# design.net
KiCad netlist of a schematic drawn in EasyEDA Pro
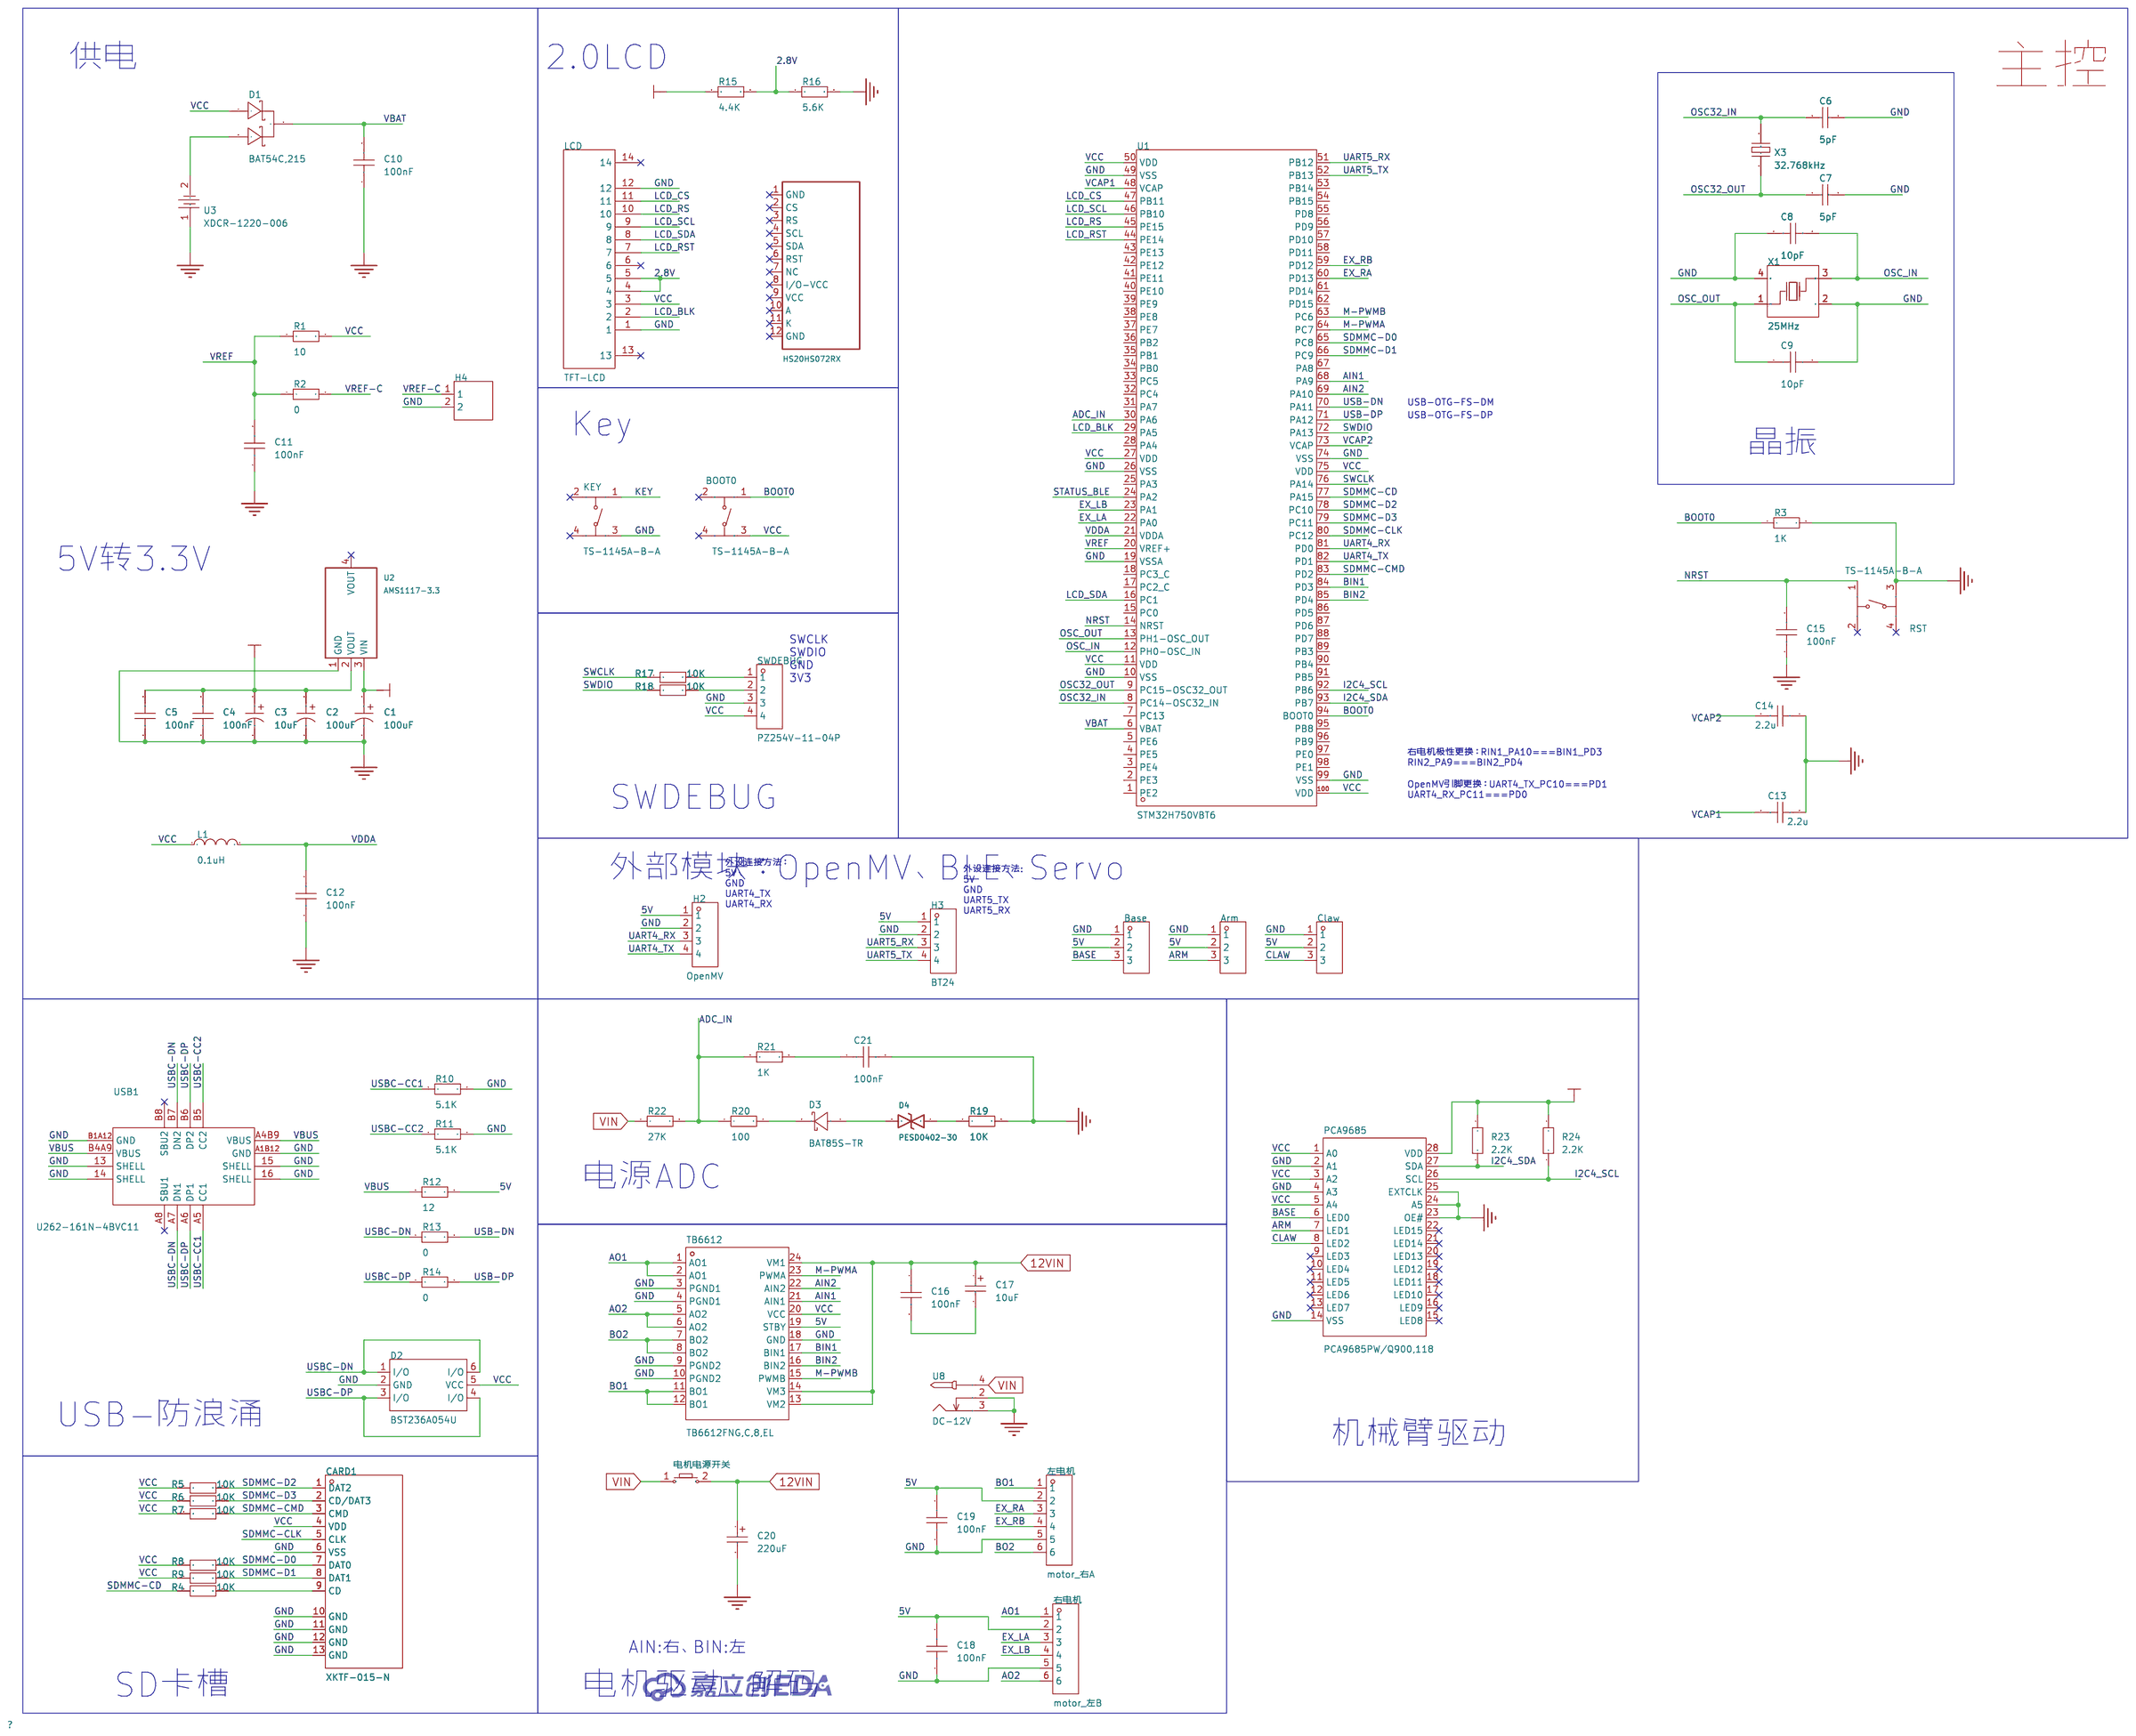
[diagram p0: schematic sheet]

(export (version "E")
  (design (tool "Eeschema 10.0.6"))
  (components
    (comp (ref "Arm")
      (value "~")
      (footprint "easyedapro:HDR-TH_3P-P2.54-V-M")
      (libsource (lib "easyedapro") (part "HDR-M_2.54_1x3P"))
    )
    (comp (ref "Base")
      (value "~")
      (footprint "easyedapro:HDR-TH_3P-P2.54-V-M")
      (libsource (lib "easyedapro") (part "HDR-M_2.54_1x3P"))
    )
    (comp (ref "BOOT0")
      (value "TS-1145A-B-A")
      (footprint "easyedapro:SW-SMD_4P-L4.2-W3.2-P2.15-LS5.2")
      (fields (field (name "Manufacturer") "XKB Connectivity(中国星坤)"))
      (libsource (lib "easyedapro") (part "TS-1145A-B-A"))
    )
    (comp (ref "C1")
      (value "100uF")
      (footprint "easyedapro:CAP-SMD_L3.5-W2.8-FD")
      (description "容值:10uF;精度:±10%;额定电压:10V;等效串联电阻:-;")
      (fields
        (field (name "Manufacturer Part") "CA45-B-10V-10UF-K")
        (field (name "Manufacturer") "CEC(振华新云)")
      )
      (libsource (lib "easyedapro") (part "CA45-B-10V-10UF-K"))
    )
    (comp (ref "C2")
      (value "100uF")
      (footprint "easyedapro:CAP-SMD_L3.5-W2.8-FD")
      (description "容值:10uF;精度:±10%;额定电压:10V;等效串联电阻:-;")
      (fields
        (field (name "Manufacturer Part") "CA45-B-10V-10UF-K")
        (field (name "Manufacturer") "CEC(振华新云)")
      )
      (libsource (lib "easyedapro") (part "CA45-B-10V-10UF-K"))
    )
    (comp (ref "C3")
      (value "10uF")
      (footprint "easyedapro:CAP-SMD_L3.5-W2.8-FD")
      (description "容值:10uF;精度:±10%;额定电压:10V;等效串联电阻:-;")
      (fields
        (field (name "Manufacturer Part") "CA45-B-10V-10UF-K")
        (field (name "Manufacturer") "CEC(振华新云)")
      )
      (libsource (lib "easyedapro") (part "CA45-B-10V-10UF-K"))
    )
    (comp (ref "C4")
      (value "100nF")
      (footprint "easyedapro:C0402")
      (libsource (lib "easyedapro") (part "Capacitance"))
    )
    (comp (ref "C5")
      (value "100nF")
      (footprint "easyedapro:C0402")
      (libsource (lib "easyedapro") (part "Capacitance"))
    )
    (comp (ref "C6")
      (value "5pF")
      (footprint "easyedapro:C0402")
      (description "容值:5pF;额定电压:50V;温度系数:C0G;")
      (fields (field (name "Manufacturer Part") "0402CG5R0C500NT") (field (name "Manufacturer") "FH(风华)"))
      (libsource (lib "easyedapro") (part "0402CG5R0C500NT"))
    )
    (comp (ref "C7")
      (value "5pF")
      (footprint "easyedapro:C0402")
      (description "容值:5pF;额定电压:50V;温度系数:C0G;")
      (fields (field (name "Manufacturer Part") "0402CG5R0C500NT") (field (name "Manufacturer") "FH(风华)"))
      (libsource (lib "easyedapro") (part "0402CG5R0C500NT"))
    )
    (comp (ref "C8")
      (value "10pF")
      (footprint "easyedapro:C0402")
      (description "容值:10pF;精度:±5%;额定电压:50V;温度系数:C0G;")
      (fields
        (field (name "Manufacturer Part") "CL05C100JB5NNNC")
        (field (name "Manufacturer") "SAMSUNG(三星)")
      )
      (libsource (lib "easyedapro") (part "CL05C100JB5NNNC"))
    )
    (comp (ref "C9")
      (value "10pF")
      (footprint "easyedapro:C0402")
      (description "容值:10pF;精度:±5%;额定电压:50V;温度系数:C0G;")
      (fields
        (field (name "Manufacturer Part") "CL05C100JB5NNNC")
        (field (name "Manufacturer") "SAMSUNG(三星)")
      )
      (libsource (lib "easyedapro") (part "CL05C100JB5NNNC"))
    )
    (comp (ref "C10")
      (value "100nF")
      (footprint "easyedapro:C0402")
      (libsource (lib "easyedapro") (part "Capacitance"))
    )
    (comp (ref "C11")
      (value "100nF")
      (footprint "easyedapro:C0402")
      (libsource (lib "easyedapro") (part "Capacitance"))
    )
    (comp (ref "C12")
      (value "100nF")
      (footprint "easyedapro:C0402")
      (libsource (lib "easyedapro") (part "Capacitance"))
    )
    (comp (ref "C13")
      (value "2.2u")
      (footprint "easyedapro:C0402")
      (libsource (lib "easyedapro") (part "Capacitance"))
    )
    (comp (ref "C14")
      (value "2.2u")
      (footprint "easyedapro:C0402")
      (libsource (lib "easyedapro") (part "Capacitance"))
    )
    (comp (ref "C15")
      (value "100nF")
      (footprint "easyedapro:C0402")
      (libsource (lib "easyedapro") (part "Capacitance"))
    )
    (comp (ref "C16")
      (value "100nF")
      (footprint "easyedapro:C0402")
      (libsource (lib "easyedapro") (part "Capacitance"))
    )
    (comp (ref "C17")
      (value "10uF")
      (footprint "easyedapro:C_Ele_SMD_3x5.4mm")
      (libsource (lib "easyedapro") (part "CAP"))
    )
    (comp (ref "C18")
      (value "100nF")
      (footprint "easyedapro:C0402")
      (libsource (lib "easyedapro") (part "Capacitance"))
    )
    (comp (ref "C19")
      (value "100nF")
      (footprint "easyedapro:C0402")
      (libsource (lib "easyedapro") (part "Capacitance"))
    )
    (comp (ref "C20")
      (value "220uF")
      (footprint "easyedapro:C_Ele_SMD_3x5.4mm")
      (libsource (lib "easyedapro") (part "CAP"))
    )
    (comp (ref "C21")
      (value "100nF")
      (footprint "easyedapro:C0402")
      (libsource (lib "easyedapro") (part "Capacitance"))
    )
    (comp (ref "CARD1")
      (value "XKTF-015-N")
      (footprint "easyedapro:TF-SMD_XKTF-015-N")
      (description "卡连接方式:自弹式;卡类型:MicroSD卡(TF卡);连接器类型:卡座;本体最大高度:2mm;工作温度:-25°C~+90°C;")
      (fields (field (name "Manufacturer") "XKB Connection(中国星坤)"))
      (libsource (lib "easyedapro") (part "XKTF-015-N"))
    )
    (comp (ref "Claw")
      (value "~")
      (footprint "easyedapro:HDR-TH_3P-P2.54-V-M")
      (libsource (lib "easyedapro") (part "HDR-M_2.54_1x3P"))
    )
    (comp (ref "D1")
      (value "BAT54C,215")
      (footprint "easyedapro:SOT-23-3_L2.9-W1.6-P1.90-LS2.8-BR")
      (description "二极管配置:1对共阴极;正向压降(Vf):800mV@100mA;直流反向耐压(Vr):30V;整流电流:200mA;")
      (fields (field (name "Manufacturer") "Nexperia(安世)"))
      (libsource (lib "easyedapro") (part "BAT54C,215"))
    )
    (comp (ref "D2")
      (value "BST236A054U")
      (footprint "easyedapro:SOT-23-6_L2.9-W1.6-P0.95-LS2.8-BR")
      (description "极性:-;反向截止电压(Vrwm):5V;钳位电压:13V;峰值脉冲电流(Ipp):3.5A;峰值脉冲功率(Ppp):45W@8/20us;击穿电压:6V;")
      (fields (field (name "Manufacturer") "BORN(伯恩半导体)"))
      (libsource (lib "easyedapro") (part "BST236A054U"))
    )
    (comp (ref "D3")
      (value "BAT85S-TR")
      (footprint "easyedapro:DO-35_BD1.7-L3.8-P7.8-D0.5-FD")
      (description "二极管配置:1个独立式;正向压降(Vf):800mV@100mA;直流反向耐压(Vr):30V;整流电流:200mA;")
      (fields (field (name "Manufacturer") "VISHAY(威世)"))
      (libsource (lib "easyedapro") (part "BAT85S-TR"))
    )
    (comp (ref "D4")
      (value "PESD0402-30")
      (footprint "easyedapro:D0402-BI")
      (description "极性:双向;反向截止电压(Vrwm):30V;钳位电压:40V;")
      (fields (field (name "Manufacturer") "R+O(宏嘉诚)"))
      (libsource (lib "easyedapro") (part "PESD0402-30"))
    )
    (comp (ref "H2")
      (value "OpenMV")
      (footprint "easyedapro:HDR-TH_4P-P2.54-V-M")
      (fields (field (name "Manufacturer") "XFCN(兴飞)"))
      (libsource (lib "easyedapro") (part "PZ254V-11-04P_C2691448"))
    )
    (comp (ref "H3")
      (value "BT24")
      (footprint "easyedapro:HDR-TH_4P-P2.54-V-M")
      (fields (field (name "Manufacturer") "XFCN(兴飞)"))
      (libsource (lib "easyedapro") (part "PZ254V-11-04P_C2691448"))
    )
    (comp (ref "H4")
      (value "~")
      (footprint "easyedapro:HDR-TH_2P-P2.54-V-M-1")
      (libsource (lib "easyedapro") (part "210S-1*2P L=11.6MMGold-plated black"))
    )
    (comp (ref "KEY")
      (value "TS-1145A-B-A")
      (footprint "easyedapro:SW-SMD_4P-L4.2-W3.2-P2.15-LS5.2")
      (fields (field (name "Manufacturer") "XKB Connectivity(中国星坤)"))
      (libsource (lib "easyedapro") (part "TS-1145A-B-A"))
    )
    (comp (ref "L1")
      (value "0.1uH")
      (footprint "easyedapro:L0805")
      (libsource (lib "easyedapro") (part "SDFL2012S100KTF"))
    )
    (comp (ref "LCD")
      (value "TFT-LCD")
      (footprint "easyedapro:FPC-SMD_AFC01-S12FCA-00")
      (description "锁定特性:翻盖式;触点类型:下接;触点数量:12P;间距:0.5mm;安装方式:卧贴;")
      (fields (field (name "Manufacturer") "JS(钜硕电子)"))
      (libsource (lib "easyedapro") (part "AFC01-S12FCA-00"))
    )
    (comp (ref "PCA9685")
      (value "PCA9685PW/Q900,118")
      (footprint "easyedapro:TSSOP-28_L9.7-W4.4-P0.65-LS6.4-BL")
      (description "类型:-;工作电压(DC):2.3V~5.5V;通道数:16;输出电压:5.5V;输出电流:25mA;调光:PWM;")
      (fields (field (name "Manufacturer") "NXP(恩智浦)"))
      (libsource (lib "easyedapro") (part "PCA9685PW/Q900,118"))
    )
    (comp (ref "R1") (value "10") (footprint "easyedapro:R0402") (libsource (lib "easyedapro") (part "电阻")))
    (comp (ref "R2") (value "0") (footprint "easyedapro:R0402") (libsource (lib "easyedapro") (part "电阻")))
    (comp (ref "R3") (value "1K") (footprint "easyedapro:R0402") (libsource (lib "easyedapro") (part "电阻")))
    (comp (ref "R4") (value "10K") (footprint "easyedapro:R0402") (libsource (lib "easyedapro") (part "电阻")))
    (comp (ref "R5") (value "10K") (footprint "easyedapro:R0402") (libsource (lib "easyedapro") (part "电阻")))
    (comp (ref "R6") (value "10K") (footprint "easyedapro:R0402") (libsource (lib "easyedapro") (part "电阻")))
    (comp (ref "R7") (value "10K") (footprint "easyedapro:R0402") (libsource (lib "easyedapro") (part "电阻")))
    (comp (ref "R8") (value "10K") (footprint "easyedapro:R0402") (libsource (lib "easyedapro") (part "电阻")))
    (comp (ref "R9") (value "10K") (footprint "easyedapro:R0402") (libsource (lib "easyedapro") (part "电阻")))
    (comp (ref "R10")
      (value "5.1K")
      (footprint "easyedapro:R0402")
      (libsource (lib "easyedapro") (part "电阻"))
    )
    (comp (ref "R11")
      (value "5.1K")
      (footprint "easyedapro:R0402")
      (libsource (lib "easyedapro") (part "电阻"))
    )
    (comp (ref "R12") (value "12") (footprint "easyedapro:R0402") (libsource (lib "easyedapro") (part "电阻")))
    (comp (ref "R13") (value "0") (footprint "easyedapro:R0402") (libsource (lib "easyedapro") (part "电阻")))
    (comp (ref "R14") (value "0") (footprint "easyedapro:R0402") (libsource (lib "easyedapro") (part "电阻")))
    (comp (ref "R15")
      (value "4.4K")
      (footprint "easyedapro:R0402")
      (libsource (lib "easyedapro") (part "电阻"))
    )
    (comp (ref "R16")
      (value "5.6K")
      (footprint "easyedapro:R0402")
      (libsource (lib "easyedapro") (part "电阻"))
    )
    (comp (ref "R17") (value "10K") (footprint "easyedapro:R0402") (libsource (lib "easyedapro") (part "电阻")))
    (comp (ref "R18") (value "10K") (footprint "easyedapro:R0402") (libsource (lib "easyedapro") (part "电阻")))
    (comp (ref "R19") (value "10K") (footprint "easyedapro:R0402") (libsource (lib "easyedapro") (part "电阻")))
    (comp (ref "R20") (value "100") (footprint "easyedapro:R0402") (libsource (lib "easyedapro") (part "电阻")))
    (comp (ref "R21") (value "1K") (footprint "easyedapro:R0402") (libsource (lib "easyedapro") (part "电阻")))
    (comp (ref "R22") (value "27K") (footprint "easyedapro:R0402") (libsource (lib "easyedapro") (part "电阻")))
    (comp (ref "R23")
      (value "2.2K")
      (footprint "easyedapro:R0402")
      (libsource (lib "easyedapro") (part "电阻"))
    )
    (comp (ref "R24")
      (value "2.2K")
      (footprint "easyedapro:R0402")
      (libsource (lib "easyedapro") (part "电阻"))
    )
    (comp (ref "RST")
      (value "TS-1145A-B-A")
      (footprint "easyedapro:SW-SMD_4P-L4.2-W3.2-P2.15-LS5.2")
      (fields (field (name "Manufacturer") "XKB Connectivity(中国星坤)"))
      (libsource (lib "easyedapro") (part "TS-1145A-B-A"))
    )
    (comp (ref "SWDEBUG")
      (value "PZ254V-11-04P")
      (footprint "easyedapro:HDR-TH_4P-P2.54-V-M")
      (fields (field (name "Manufacturer") "XFCN(兴飞)"))
      (libsource (lib "easyedapro") (part "PZ254V-11-04P_C2691448"))
    )
    (comp (ref "TB6612")
      (value "TB6612FNG,C,8,EL")
      (footprint "easyedapro:SSOP-24_L8.3-W5.6-P0.65-LS7.6-BL")
      (description "TB6612FNG 是一款直流电机驱动 IC，其输出晶体管采用低导通电阻的 LD MOS 结构。两个输入信号 IN1 和 IN2 可选择四种模式之一，如正转、反转、短路制动和停止模式。")
      (fields (field (name "Manufacturer") "TOSHIBA(东芝)"))
      (libsource (lib "easyedapro") (part "TB6612FNG,C,8,EL"))
    )
    (comp (ref "U1")
      (value "STM32H750VBT6")
      (footprint "easyedapro:LQFP-100_L14.0-W14.0-P0.50-LS16.0-BL")
      (description "CPU内核:ARM-M系列;CPU最大主频:480MHz;应用领域:-;")
      (fields (field (name "Manufacturer") "ST(意法半导体)"))
      (libsource (lib "easyedapro") (part "STM32H750VBT6"))
    )
    (comp (ref "U2")
      (value "AMS1117-3.3")
      (footprint "easyedapro:SOT-223-3_L6.5-W3.4-P2.30-LS7.0-BR")
      (description "输出极性:正极;工作电压:15V;输出电压:3.3V;输出电流:1A;电源纹波抑制比(PSRR):72dB@(120Hz);输出类型:固定;")
      (fields (field (name "Manufacturer") "Advanced Monolithic Systems"))
      (libsource (lib "easyedapro") (part "AMS1117-3.3"))
    )
    (comp (ref "U3")
      (value "XDCR-1220-006")
      (footprint "easyedapro:BAT-SMD_CR1220-2ZX")
      (description "连接器类型:电池底座;适用电池规格:CR1220;触头材质:-;触头镀层:金;工作温度:-40°C~+85°C;")
      (fields (field (name "Manufacturer") "LX(连欣科技)"))
      (libsource (lib "easyedapro") (part "XDCR-1220-006"))
    )
    (comp (ref "U7")
      (value "HS20HS072RX")
      (footprint "easyedapro:OLED-SMD_HS20HS072RX")
      (description "核心芯片:ST7789;接口类型:SPI;尺寸(inch):2;像素分辨率:320x240;")
      (fields (field (name "Manufacturer") "HS(汉昇)"))
      (libsource (lib "easyedapro") (part "HS20HS072RX"))
    )
    (comp (ref "U8")
      (value "DC-12V")
      (footprint "easyedapro:DC-IN-TH_DC005-2.5MM")
      (description "连接器类型:DC电源插座;安装方式:弯插;触点内径:2.5mm;触点外径:6.3mm;额定电流:500mA;额定电压:12V;工作温度:-30°C~+70°C;")
      (fields (field (name "Manufacturer") "SHOU HAN(首韩)"))
      (libsource (lib "easyedapro") (part "DC005-2.5"))
    )
    (comp (ref "USB1")
      (value "U262-161N-4BVC11")
      (footprint "easyedapro:USB-3.1-SMD_U262-161N-4BVC11")
      (description "连接器类型:Type-C;协议标准:-;公母:母;安装方式:卧贴;触点数量:16P;端口数量:1;额定电流 - 电源:3A;工作温度:-40°C~+85°C;")
      (fields (field (name "Manufacturer") "XKB Connection(中国星坤)"))
      (libsource (lib "easyedapro") (part "U262-16XN-4BVC11"))
    )
    (comp (ref "X1")
      (value "25MHz")
      (footprint "easyedapro:CRYSTAL-SMD_4P-L3.2-W2.5-BL")
      (description "晶振类型:贴片晶振;频率:25MHz;常温频差:±10ppm;负载电容:12pF;频率稳定度:±20ppm;")
      (fields (field (name "Manufacturer Part") "X322525MOB4SI") (field (name "Manufacturer") "YXC(扬兴晶振)"))
      (libsource (lib "easyedapro") (part "X322525MOB4SI"))
    )
    (comp (ref "X3")
      (value "32.768kHz")
      (footprint "easyedapro:CRYSTAL-SMD_L3.2-W1.5-1")
      (description "频率:32.768kHz;常温频差:±20ppm;负载电容:12.5pF;")
      (fields
        (field (name "Manufacturer Part") "FC-135R 32.7680KA-A3")
        (field (name "Manufacturer") "EPSON(爱普生)")
      )
      (libsource (lib "easyedapro") (part "FC-135R 32.7680KA-A3"))
    )
    (comp (ref "右电机")
      (value "motor_左B")
      (footprint "easyedapro:CONN-TH_6P-P2.50_ZX-XH2.54-6PZZ")
      (fields (field (name "Manufacturer") "Megastar(兆星)"))
      (libsource (lib "easyedapro") (part "ZX-XH2.54-6PZZ"))
    )
    (comp (ref "左电机")
      (value "motor_右A")
      (footprint "easyedapro:CONN-TH_6P-P2.50_ZX-XH2.54-6PZZ")
      (fields (field (name "Manufacturer") "Megastar(兆星)"))
      (libsource (lib "easyedapro") (part "ZX-XH2.54-6PZZ"))
    )
    (comp (ref "电机电源开关")
      (value "~")
      (footprint "easyedapro:Key_SMD_3x4x2")
      (libsource (lib "easyedapro") (part "轻触按键x2"))
    )
  )
  (nets
    (net (code "1") (name "/2.8V") (class "Default")
      (node (ref "LCD") (pin "4") (pinfunction "4_4") (pintype "unspecified"))
      (node (ref "LCD") (pin "5") (pinfunction "5_5") (pintype "unspecified"))
      (node (ref "R15") (pin "2") (pinfunction "2_2") (pintype "input"))
      (node (ref "R16") (pin "1") (pinfunction "1_1") (pintype "input"))
    )
    (net (code "2") (name "/ADC_IN") (class "Default")
      (node (ref "R20") (pin "1") (pinfunction "1_1") (pintype "input"))
      (node (ref "R21") (pin "1") (pinfunction "1_1") (pintype "input"))
      (node (ref "R22") (pin "2") (pinfunction "2_2") (pintype "input"))
      (node (ref "U1") (pin "30") (pinfunction "PA6_30") (pintype "unspecified"))
    )
    (net (code "3") (name "/AIN1") (class "Default")
      (node (ref "TB6612") (pin "21") (pinfunction "AIN1_21") (pintype "unspecified"))
      (node (ref "U1") (pin "68") (pinfunction "PA9_68") (pintype "unspecified"))
    )
    (net (code "4") (name "/AIN2") (class "Default")
      (node (ref "TB6612") (pin "22") (pinfunction "AIN2_22") (pintype "unspecified"))
      (node (ref "U1") (pin "69") (pinfunction "PA10_69") (pintype "unspecified"))
    )
    (net (code "5") (name "/AO1") (class "Default")
      (node (ref "TB6612") (pin "1") (pinfunction "AO1_1") (pintype "unspecified"))
      (node (ref "TB6612") (pin "2") (pinfunction "AO1_2") (pintype "unspecified"))
      (node (ref "右电机") (pin "1") (pinfunction "1_1") (pintype "unspecified"))
    )
    (net (code "6") (name "/AO2") (class "Default")
      (node (ref "TB6612") (pin "5") (pinfunction "AO2_5") (pintype "unspecified"))
      (node (ref "TB6612") (pin "6") (pinfunction "AO2_6") (pintype "unspecified"))
      (node (ref "右电机") (pin "6") (pinfunction "6_6") (pintype "unspecified"))
    )
    (net (code "7") (name "/ARM") (class "Default")
      (node (ref "Arm") (pin "3") (pinfunction "3_3") (pintype "input"))
      (node (ref "PCA9685") (pin "7") (pinfunction "LED1_7") (pintype "unspecified"))
    )
    (net (code "8") (name "/BASE") (class "Default")
      (node (ref "Base") (pin "3") (pinfunction "3_3") (pintype "input"))
      (node (ref "PCA9685") (pin "6") (pinfunction "LED0_6") (pintype "unspecified"))
    )
    (net (code "9") (name "/BIN1") (class "Default")
      (node (ref "TB6612") (pin "17") (pinfunction "BIN1_17") (pintype "unspecified"))
      (node (ref "U1") (pin "84") (pinfunction "PD3_84") (pintype "unspecified"))
    )
    (net (code "10") (name "/BIN2") (class "Default")
      (node (ref "TB6612") (pin "16") (pinfunction "BIN2_16") (pintype "unspecified"))
      (node (ref "U1") (pin "85") (pinfunction "PD4_85") (pintype "unspecified"))
    )
    (net (code "11") (name "/BO1") (class "Default")
      (node (ref "TB6612") (pin "11") (pinfunction "BO1_11") (pintype "unspecified"))
      (node (ref "TB6612") (pin "12") (pinfunction "BO1_12") (pintype "unspecified"))
      (node (ref "左电机") (pin "1") (pinfunction "1_1") (pintype "unspecified"))
    )
    (net (code "12") (name "/BO2") (class "Default")
      (node (ref "TB6612") (pin "7") (pinfunction "BO2_7") (pintype "unspecified"))
      (node (ref "TB6612") (pin "8") (pinfunction "BO2_8") (pintype "unspecified"))
      (node (ref "左电机") (pin "6") (pinfunction "6_6") (pintype "unspecified"))
    )
    (net (code "13") (name "/BOOT0") (class "Default")
      (node (ref "BOOT0") (pin "1") (pinfunction "1_1") (pintype "unspecified"))
      (node (ref "R3") (pin "1") (pinfunction "1_1") (pintype "input"))
      (node (ref "U1") (pin "94") (pinfunction "BOOT0_94") (pintype "unspecified"))
    )
    (net (code "14") (name "/CLAW") (class "Default")
      (node (ref "Claw") (pin "3") (pinfunction "3_3") (pintype "input"))
      (node (ref "PCA9685") (pin "8") (pinfunction "LED2_8") (pintype "unspecified"))
    )
    (net (code "15") (name "/EX_LA") (class "Default")
      (node (ref "U1") (pin "22") (pinfunction "PA0_22") (pintype "unspecified"))
      (node (ref "右电机") (pin "3") (pinfunction "3_3") (pintype "unspecified"))
    )
    (net (code "16") (name "/EX_LB") (class "Default")
      (node (ref "U1") (pin "23") (pinfunction "PA1_23") (pintype "unspecified"))
      (node (ref "右电机") (pin "4") (pinfunction "4_4") (pintype "unspecified"))
    )
    (net (code "17") (name "/EX_RA") (class "Default")
      (node (ref "U1") (pin "60") (pinfunction "PD13_60") (pintype "unspecified"))
      (node (ref "左电机") (pin "3") (pinfunction "3_3") (pintype "unspecified"))
    )
    (net (code "18") (name "/EX_RB") (class "Default")
      (node (ref "U1") (pin "59") (pinfunction "PD12_59") (pintype "unspecified"))
      (node (ref "左电机") (pin "4") (pinfunction "4_4") (pintype "unspecified"))
    )
    (net (code "19") (name "/I2C4_SCL") (class "Default")
      (node (ref "PCA9685") (pin "26") (pinfunction "SCL_26") (pintype "unspecified"))
      (node (ref "R24") (pin "1") (pinfunction "1_1") (pintype "input"))
      (node (ref "U1") (pin "92") (pinfunction "PB6_92") (pintype "unspecified"))
    )
    (net (code "20") (name "/I2C4_SDA") (class "Default")
      (node (ref "PCA9685") (pin "27") (pinfunction "SDA_27") (pintype "unspecified"))
      (node (ref "R23") (pin "1") (pinfunction "1_1") (pintype "input"))
      (node (ref "U1") (pin "93") (pinfunction "PB7_93") (pintype "unspecified"))
    )
    (net (code "21") (name "/KEY") (class "Default")
      (node (ref "KEY") (pin "1") (pinfunction "1_1") (pintype "unspecified"))
    )
    (net (code "22") (name "/LCD_BLK") (class "Default")
      (node (ref "LCD") (pin "2") (pinfunction "2_2") (pintype "unspecified"))
      (node (ref "U1") (pin "29") (pinfunction "PA5_29") (pintype "unspecified"))
    )
    (net (code "23") (name "/LCD_CS") (class "Default")
      (node (ref "LCD") (pin "11") (pinfunction "11_11") (pintype "unspecified"))
      (node (ref "U1") (pin "47") (pinfunction "PB11_47") (pintype "unspecified"))
    )
    (net (code "24") (name "/LCD_RS") (class "Default")
      (node (ref "LCD") (pin "10") (pinfunction "10_10") (pintype "unspecified"))
      (node (ref "U1") (pin "45") (pinfunction "PE15_45") (pintype "unspecified"))
    )
    (net (code "25") (name "/LCD_RST") (class "Default")
      (node (ref "LCD") (pin "7") (pinfunction "7_7") (pintype "unspecified"))
      (node (ref "U1") (pin "44") (pinfunction "PE14_44") (pintype "unspecified"))
    )
    (net (code "26") (name "/LCD_SCL") (class "Default")
      (node (ref "LCD") (pin "9") (pinfunction "9_9") (pintype "unspecified"))
      (node (ref "U1") (pin "46") (pinfunction "PB10_46") (pintype "unspecified"))
    )
    (net (code "27") (name "/LCD_SDA") (class "Default")
      (node (ref "LCD") (pin "8") (pinfunction "8_8") (pintype "unspecified"))
      (node (ref "U1") (pin "16") (pinfunction "PC1_16") (pintype "unspecified"))
    )
    (net (code "28") (name "/M-PWMA") (class "Default")
      (node (ref "TB6612") (pin "23") (pinfunction "PWMA_23") (pintype "unspecified"))
      (node (ref "U1") (pin "64") (pinfunction "PC7_64") (pintype "unspecified"))
    )
    (net (code "29") (name "/M-PWMB") (class "Default")
      (node (ref "TB6612") (pin "15") (pinfunction "PWMB_15") (pintype "unspecified"))
      (node (ref "U1") (pin "63") (pinfunction "PC6_63") (pintype "unspecified"))
    )
    (net (code "30") (name "/NRST") (class "Default")
      (node (ref "C15") (pin "2") (pinfunction "2_2") (pintype "input"))
      (node (ref "RST") (pin "1") (pinfunction "1_1") (pintype "unspecified"))
      (node (ref "U1") (pin "14") (pinfunction "NRST_14") (pintype "unspecified"))
    )
    (net (code "31") (name "/OSC32_IN") (class "Default")
      (node (ref "C6") (pin "1") (pinfunction "1_1") (pintype "input"))
      (node (ref "U1") (pin "8") (pinfunction "PC14-OSC32_IN_8") (pintype "unspecified"))
      (node (ref "X3") (pin "2") (pinfunction "GND_2") (pintype "input"))
    )
    (net (code "32") (name "/OSC32_OUT") (class "Default")
      (node (ref "C7") (pin "1") (pinfunction "1_1") (pintype "input"))
      (node (ref "U1") (pin "9") (pinfunction "PC15-OSC32_OUT_9") (pintype "unspecified"))
      (node (ref "X3") (pin "1") (pinfunction "1_1") (pintype "input"))
    )
    (net (code "33") (name "/OSC_IN") (class "Default")
      (node (ref "C8") (pin "2") (pinfunction "2_2") (pintype "unspecified"))
      (node (ref "U1") (pin "12") (pinfunction "PH0-OSC_IN_12") (pintype "unspecified"))
      (node (ref "X1") (pin "3") (pinfunction "OSC2_3") (pintype "unspecified"))
    )
    (net (code "34") (name "/OSC_OUT") (class "Default")
      (node (ref "C9") (pin "1") (pinfunction "1_1") (pintype "unspecified"))
      (node (ref "U1") (pin "13") (pinfunction "PH1-OSC_OUT_13") (pintype "unspecified"))
      (node (ref "X1") (pin "1") (pinfunction "OSC1_1") (pintype "unspecified"))
    )
    (net (code "35") (name "/SDMMC-CD") (class "Default")
      (node (ref "R4") (pin "1") (pinfunction "1_1") (pintype "input"))
      (node (ref "U1") (pin "77") (pinfunction "PA15_77") (pintype "unspecified"))
    )
    (net (code "36") (name "/SDMMC-CLK") (class "Default")
      (node (ref "CARD1") (pin "5") (pinfunction "CLK_5") (pintype "unspecified"))
      (node (ref "U1") (pin "80") (pinfunction "PC12_80") (pintype "unspecified"))
    )
    (net (code "37") (name "/SDMMC-CMD") (class "Default")
      (node (ref "CARD1") (pin "3") (pinfunction "CMD_3") (pintype "unspecified"))
      (node (ref "R7") (pin "2") (pinfunction "2_2") (pintype "input"))
      (node (ref "U1") (pin "83") (pinfunction "PD2_83") (pintype "unspecified"))
    )
    (net (code "38") (name "/SDMMC-D0") (class "Default")
      (node (ref "CARD1") (pin "7") (pinfunction "DAT0_7") (pintype "unspecified"))
      (node (ref "R8") (pin "2") (pinfunction "2_2") (pintype "input"))
      (node (ref "U1") (pin "65") (pinfunction "PC8_65") (pintype "unspecified"))
    )
    (net (code "39") (name "/SDMMC-D1") (class "Default")
      (node (ref "CARD1") (pin "8") (pinfunction "DAT1_8") (pintype "unspecified"))
      (node (ref "R9") (pin "2") (pinfunction "2_2") (pintype "input"))
      (node (ref "U1") (pin "66") (pinfunction "PC9_66") (pintype "unspecified"))
    )
    (net (code "40") (name "/SDMMC-D2") (class "Default")
      (node (ref "CARD1") (pin "1") (pinfunction "DAT2_1") (pintype "unspecified"))
      (node (ref "R5") (pin "2") (pinfunction "2_2") (pintype "input"))
      (node (ref "U1") (pin "78") (pinfunction "PC10_78") (pintype "unspecified"))
    )
    (net (code "41") (name "/SDMMC-D3") (class "Default")
      (node (ref "CARD1") (pin "2") (pinfunction "CD/DAT3_2") (pintype "unspecified"))
      (node (ref "R6") (pin "2") (pinfunction "2_2") (pintype "input"))
      (node (ref "U1") (pin "79") (pinfunction "PC11_79") (pintype "unspecified"))
    )
    (net (code "42") (name "/STATUS_BLE") (class "Default")
      (node (ref "U1") (pin "24") (pinfunction "PA2_24") (pintype "unspecified"))
    )
    (net (code "43") (name "/SWCLK") (class "Default")
      (node (ref "R17") (pin "1") (pinfunction "1_1") (pintype "input"))
      (node (ref "U1") (pin "76") (pinfunction "PA14_76") (pintype "unspecified"))
    )
    (net (code "44") (name "/SWDIO") (class "Default")
      (node (ref "R18") (pin "1") (pinfunction "1_1") (pintype "input"))
      (node (ref "U1") (pin "72") (pinfunction "PA13_72") (pintype "unspecified"))
    )
    (net (code "45") (name "/UART4_RX") (class "Default")
      (node (ref "H2") (pin "3") (pinfunction "3_3") (pintype "unspecified"))
      (node (ref "U1") (pin "81") (pinfunction "PD0_81") (pintype "unspecified"))
    )
    (net (code "46") (name "/UART4_TX") (class "Default")
      (node (ref "H2") (pin "4") (pinfunction "4_4") (pintype "unspecified"))
      (node (ref "U1") (pin "82") (pinfunction "PD1_82") (pintype "unspecified"))
    )
    (net (code "47") (name "/UART5_RX") (class "Default")
      (node (ref "H3") (pin "3") (pinfunction "3_3") (pintype "unspecified"))
      (node (ref "U1") (pin "51") (pinfunction "PB12_51") (pintype "unspecified"))
    )
    (net (code "48") (name "/UART5_TX") (class "Default")
      (node (ref "H3") (pin "4") (pinfunction "4_4") (pintype "unspecified"))
      (node (ref "U1") (pin "52") (pinfunction "PB13_52") (pintype "unspecified"))
    )
    (net (code "49") (name "/USB-DN") (class "Default")
      (node (ref "R13") (pin "2") (pinfunction "2_2") (pintype "input"))
      (node (ref "U1") (pin "70") (pinfunction "PA11_70") (pintype "unspecified"))
    )
    (net (code "50") (name "/USB-DP") (class "Default")
      (node (ref "R14") (pin "2") (pinfunction "2_2") (pintype "input"))
      (node (ref "U1") (pin "71") (pinfunction "PA12_71") (pintype "unspecified"))
    )
    (net (code "51") (name "/USBC-CC1") (class "Default")
      (node (ref "R10") (pin "1") (pinfunction "1_1") (pintype "input"))
      (node (ref "USB1") (pin "A5") (pinfunction "CC1_A5") (pintype "unspecified"))
    )
    (net (code "52") (name "/USBC-CC2") (class "Default")
      (node (ref "R11") (pin "1") (pinfunction "1_1") (pintype "input"))
      (node (ref "USB1") (pin "B5") (pinfunction "CC2_B5") (pintype "unspecified"))
    )
    (net (code "53") (name "/USBC-DN") (class "Default")
      (node (ref "D2") (pin "1") (pinfunction "I/O_1") (pintype "unspecified"))
      (node (ref "D2") (pin "6") (pinfunction "I/O_6") (pintype "unspecified"))
      (node (ref "R13") (pin "1") (pinfunction "1_1") (pintype "input"))
      (node (ref "USB1") (pin "A7") (pinfunction "DN1_A7") (pintype "unspecified"))
      (node (ref "USB1") (pin "B7") (pinfunction "DN2_B7") (pintype "unspecified"))
    )
    (net (code "54") (name "/USBC-DP") (class "Default")
      (node (ref "D2") (pin "3") (pinfunction "I/O_3") (pintype "unspecified"))
      (node (ref "D2") (pin "4") (pinfunction "I/O_4") (pintype "unspecified"))
      (node (ref "R14") (pin "1") (pinfunction "1_1") (pintype "input"))
      (node (ref "USB1") (pin "A6") (pinfunction "DP1_A6") (pintype "unspecified"))
      (node (ref "USB1") (pin "B6") (pinfunction "DP2_B6") (pintype "unspecified"))
    )
    (net (code "55") (name "/VBAT") (class "Default")
      (node (ref "C10") (pin "2") (pinfunction "2_2") (pintype "input"))
      (node (ref "D1") (pin "3") (pinfunction "K_3") (pintype "unspecified"))
      (node (ref "U1") (pin "6") (pinfunction "VBAT_6") (pintype "unspecified"))
    )
    (net (code "56") (name "/VBUS") (class "Default")
      (node (ref "R12") (pin "1") (pinfunction "1_1") (pintype "input"))
      (node (ref "USB1") (pin "A4B9") (pinfunction "VBUS_A4B9") (pintype "unspecified"))
      (node (ref "USB1") (pin "B4A9") (pinfunction "VBUS_B4A9") (pintype "unspecified"))
    )
    (net (code "57") (name "/VCAP1") (class "Default")
      (node (ref "C13") (pin "2") (pinfunction "2_2") (pintype "input"))
      (node (ref "U1") (pin "48") (pinfunction "VCAP_48") (pintype "unspecified"))
    )
    (net (code "58") (name "/VCAP2") (class "Default")
      (node (ref "C14") (pin "2") (pinfunction "2_2") (pintype "input"))
      (node (ref "U1") (pin "73") (pinfunction "VCAP_73") (pintype "unspecified"))
    )
    (net (code "59") (name "/VDDA") (class "Default")
      (node (ref "C12") (pin "2") (pinfunction "2_2") (pintype "input"))
      (node (ref "L1") (pin "2") (pinfunction "2_2") (pintype "unspecified"))
      (node (ref "U1") (pin "21") (pinfunction "VDDA_21") (pintype "unspecified"))
    )
    (net (code "60") (name "/VREF") (class "Default")
      (node (ref "C11") (pin "2") (pinfunction "2_2") (pintype "input"))
      (node (ref "R1") (pin "1") (pinfunction "1_1") (pintype "input"))
      (node (ref "R2") (pin "1") (pinfunction "1_1") (pintype "input"))
      (node (ref "U1") (pin "20") (pinfunction "VREF+_20") (pintype "unspecified"))
    )
    (net (code "61") (name "/VREF-C") (class "Default")
      (node (ref "H4") (pin "1") (pinfunction "1_1") (pintype "unspecified"))
      (node (ref "R2") (pin "2") (pinfunction "2_2") (pintype "input"))
    )
    (net (code "62") (name "5V") (class "Default")
      (node (ref "Arm") (pin "2") (pinfunction "2_2") (pintype "input"))
      (node (ref "Base") (pin "2") (pinfunction "2_2") (pintype "input"))
      (node (ref "C1") (pin "1") (pinfunction "1_1") (pintype "input"))
      (node (ref "C18") (pin "2") (pinfunction "2_2") (pintype "input"))
      (node (ref "C19") (pin "2") (pinfunction "2_2") (pintype "input"))
      (node (ref "Claw") (pin "2") (pinfunction "2_2") (pintype "input"))
      (node (ref "H2") (pin "1") (pinfunction "1_1") (pintype "unspecified"))
      (node (ref "H3") (pin "1") (pinfunction "1_1") (pintype "unspecified"))
      (node (ref "R12") (pin "2") (pinfunction "2_2") (pintype "input"))
      (node (ref "R15") (pin "1") (pinfunction "1_1") (pintype "input"))
      (node (ref "TB6612") (pin "19") (pinfunction "STBY_19") (pintype "unspecified"))
      (node (ref "U2") (pin "3") (pinfunction "VIN_3") (pintype "unspecified"))
      (node (ref "右电机") (pin "2") (pinfunction "2_2") (pintype "unspecified"))
      (node (ref "左电机") (pin "2") (pinfunction "2_2") (pintype "unspecified"))
    )
    (net (code "63") (name "12VIN") (class "Default")
      (node (ref "C16") (pin "1") (pinfunction "1_1") (pintype "input"))
      (node (ref "C17") (pin "1") (pinfunction "1_1") (pintype "input"))
      (node (ref "C20") (pin "1") (pinfunction "1_1") (pintype "input"))
      (node (ref "TB6612") (pin "13") (pinfunction "VM2_13") (pintype "unspecified"))
      (node (ref "TB6612") (pin "14") (pinfunction "VM3_14") (pintype "unspecified"))
      (node (ref "TB6612") (pin "24") (pinfunction "VM1_24") (pintype "unspecified"))
      (node (ref "电机电源开关") (pin "2") (pinfunction "2_2") (pintype "input"))
    )
    (net (code "64") (name "GND") (class "Default")
      (node (ref "Arm") (pin "1") (pinfunction "1_1") (pintype "input"))
      (node (ref "Base") (pin "1") (pinfunction "1_1") (pintype "input"))
      (node (ref "C1") (pin "2") (pinfunction "2_2") (pintype "input"))
      (node (ref "C10") (pin "1") (pinfunction "1_1") (pintype "input"))
      (node (ref "C11") (pin "1") (pinfunction "1_1") (pintype "input"))
      (node (ref "C12") (pin "1") (pinfunction "1_1") (pintype "input"))
      (node (ref "C13") (pin "1") (pinfunction "1_1") (pintype "input"))
      (node (ref "C14") (pin "1") (pinfunction "1_1") (pintype "input"))
      (node (ref "C15") (pin "1") (pinfunction "1_1") (pintype "input"))
      (node (ref "C18") (pin "1") (pinfunction "1_1") (pintype "input"))
      (node (ref "C19") (pin "1") (pinfunction "1_1") (pintype "input"))
      (node (ref "C2") (pin "2") (pinfunction "2_2") (pintype "input"))
      (node (ref "C20") (pin "2") (pinfunction "2_2") (pintype "input"))
      (node (ref "C21") (pin "2") (pinfunction "2_2") (pintype "input"))
      (node (ref "C3") (pin "2") (pinfunction "2_2") (pintype "input"))
      (node (ref "C4") (pin "1") (pinfunction "1_1") (pintype "input"))
      (node (ref "C5") (pin "1") (pinfunction "1_1") (pintype "input"))
      (node (ref "C6") (pin "2") (pinfunction "2_2") (pintype "input"))
      (node (ref "C7") (pin "2") (pinfunction "2_2") (pintype "input"))
      (node (ref "C8") (pin "1") (pinfunction "1_1") (pintype "unspecified"))
      (node (ref "C9") (pin "2") (pinfunction "2_2") (pintype "unspecified"))
      (node (ref "CARD1") (pin "10") (pinfunction "GND_10") (pintype "unspecified"))
      (node (ref "CARD1") (pin "11") (pinfunction "GND_11") (pintype "unspecified"))
      (node (ref "CARD1") (pin "12") (pinfunction "GND_12") (pintype "unspecified"))
      (node (ref "CARD1") (pin "13") (pinfunction "GND_13") (pintype "unspecified"))
      (node (ref "CARD1") (pin "6") (pinfunction "VSS_6") (pintype "unspecified"))
      (node (ref "Claw") (pin "1") (pinfunction "1_1") (pintype "input"))
      (node (ref "D2") (pin "2") (pinfunction "GND_2") (pintype "unspecified"))
      (node (ref "H2") (pin "2") (pinfunction "2_2") (pintype "unspecified"))
      (node (ref "H3") (pin "2") (pinfunction "2_2") (pintype "unspecified"))
      (node (ref "H4") (pin "2") (pinfunction "2_2") (pintype "unspecified"))
      (node (ref "KEY") (pin "3") (pinfunction "3_3") (pintype "unspecified"))
      (node (ref "LCD") (pin "1") (pinfunction "1_1") (pintype "unspecified"))
      (node (ref "LCD") (pin "12") (pinfunction "12_12") (pintype "unspecified"))
      (node (ref "PCA9685") (pin "14") (pinfunction "VSS_14") (pintype "unspecified"))
      (node (ref "PCA9685") (pin "2") (pinfunction "A1_2") (pintype "unspecified"))
      (node (ref "PCA9685") (pin "23") (pinfunction "OE#_23") (pintype "unspecified"))
      (node (ref "PCA9685") (pin "24") (pinfunction "A5_24") (pintype "unspecified"))
      (node (ref "PCA9685") (pin "25") (pinfunction "EXTCLK_25") (pintype "unspecified"))
      (node (ref "PCA9685") (pin "4") (pinfunction "A3_4") (pintype "unspecified"))
      (node (ref "R10") (pin "2") (pinfunction "2_2") (pintype "input"))
      (node (ref "R11") (pin "2") (pinfunction "2_2") (pintype "input"))
      (node (ref "R16") (pin "2") (pinfunction "2_2") (pintype "input"))
      (node (ref "R19") (pin "2") (pinfunction "2_2") (pintype "input"))
      (node (ref "R3") (pin "2") (pinfunction "2_2") (pintype "input"))
      (node (ref "RST") (pin "3") (pinfunction "3_3") (pintype "unspecified"))
      (node (ref "SWDEBUG") (pin "3") (pinfunction "3_3") (pintype "unspecified"))
      (node (ref "TB6612") (pin "10") (pinfunction "PGND2_10") (pintype "unspecified"))
      (node (ref "TB6612") (pin "18") (pinfunction "GND_18") (pintype "unspecified"))
      (node (ref "TB6612") (pin "3") (pinfunction "PGND1_3") (pintype "unspecified"))
      (node (ref "TB6612") (pin "4") (pinfunction "PGND1_4") (pintype "unspecified"))
      (node (ref "TB6612") (pin "9") (pinfunction "PGND2_9") (pintype "unspecified"))
      (node (ref "U1") (pin "10") (pinfunction "VSS_10") (pintype "unspecified"))
      (node (ref "U1") (pin "19") (pinfunction "VSSA_19") (pintype "unspecified"))
      (node (ref "U1") (pin "26") (pinfunction "VSS_26") (pintype "unspecified"))
      (node (ref "U1") (pin "49") (pinfunction "VSS_49") (pintype "unspecified"))
      (node (ref "U1") (pin "74") (pinfunction "VSS_74") (pintype "unspecified"))
      (node (ref "U1") (pin "99") (pinfunction "VSS_99") (pintype "unspecified"))
      (node (ref "U2") (pin "1") (pinfunction "GND_1") (pintype "unspecified"))
      (node (ref "U3") (pin "1") (pinfunction "1_1") (pintype "input"))
      (node (ref "U8") (pin "2") (pinfunction "2_2") (pintype "unspecified"))
      (node (ref "U8") (pin "3") (pinfunction "3_3") (pintype "unspecified"))
      (node (ref "USB1") (pin "13") (pinfunction "SHELL_13") (pintype "unspecified"))
      (node (ref "USB1") (pin "14") (pinfunction "SHELL_14") (pintype "unspecified"))
      (node (ref "USB1") (pin "15") (pinfunction "SHELL_15") (pintype "unspecified"))
      (node (ref "USB1") (pin "16") (pinfunction "SHELL_16") (pintype "unspecified"))
      (node (ref "USB1") (pin "A1B12") (pinfunction "GND_A1B12") (pintype "unspecified"))
      (node (ref "USB1") (pin "B1A12") (pinfunction "GND_B1A12") (pintype "unspecified"))
      (node (ref "X1") (pin "2") (pinfunction "GND_2") (pintype "unspecified"))
      (node (ref "X1") (pin "4") (pinfunction "GND_4") (pintype "unspecified"))
      (node (ref "右电机") (pin "5") (pinfunction "5_5") (pintype "unspecified"))
      (node (ref "左电机") (pin "5") (pinfunction "5_5") (pintype "unspecified"))
    )
    (net (code "65") (name "Net-(C16-Pad2)") (class "Default")
      (node (ref "C16") (pin "2") (pinfunction "2_2") (pintype "input"))
      (node (ref "C17") (pin "2") (pinfunction "2_2") (pintype "input"))
    )
    (net (code "66") (name "Net-(C21-Pad1)") (class "Default")
      (node (ref "C21") (pin "1") (pinfunction "1_1") (pintype "input"))
      (node (ref "R21") (pin "2") (pinfunction "2_2") (pintype "input"))
    )
    (net (code "67") (name "Net-(CARD1-CD)") (class "Default")
      (node (ref "CARD1") (pin "9") (pinfunction "CD_9") (pintype "unspecified"))
      (node (ref "R4") (pin "2") (pinfunction "2_2") (pintype "input"))
    )
    (net (code "68") (name "Net-(D1-A-Pad2)") (class "Default")
      (node (ref "D1") (pin "2") (pinfunction "A_2") (pintype "unspecified"))
      (node (ref "U3") (pin "2") (pinfunction "2_2") (pintype "input"))
    )
    (net (code "69") (name "Net-(D3-A)") (class "Default")
      (node (ref "D3") (pin "1") (pinfunction "A_1") (pintype "unspecified"))
      (node (ref "D4") (pin "2") (pinfunction "2_2") (pintype "unspecified"))
    )
    (net (code "70") (name "Net-(D3-K)") (class "Default")
      (node (ref "D3") (pin "2") (pinfunction "K_2") (pintype "unspecified"))
      (node (ref "R20") (pin "2") (pinfunction "2_2") (pintype "input"))
    )
    (net (code "71") (name "Net-(D4-Pad1)") (class "Default")
      (node (ref "D4") (pin "1") (pinfunction "1_1") (pintype "unspecified"))
      (node (ref "R19") (pin "1") (pinfunction "1_1") (pintype "input"))
    )
    (net (code "72") (name "Net-(R17-Pad2)") (class "Default")
      (node (ref "R17") (pin "2") (pinfunction "2_2") (pintype "input"))
      (node (ref "SWDEBUG") (pin "1") (pinfunction "1_1") (pintype "unspecified"))
    )
    (net (code "73") (name "Net-(R18-Pad2)") (class "Default")
      (node (ref "R18") (pin "2") (pinfunction "2_2") (pintype "input"))
      (node (ref "SWDEBUG") (pin "2") (pinfunction "2_2") (pintype "unspecified"))
    )
    (net (code "74") (name "VCC") (class "Default")
      (node (ref "BOOT0") (pin "3") (pinfunction "3_3") (pintype "unspecified"))
      (node (ref "C2") (pin "1") (pinfunction "1_1") (pintype "input"))
      (node (ref "C3") (pin "1") (pinfunction "1_1") (pintype "input"))
      (node (ref "C4") (pin "2") (pinfunction "2_2") (pintype "input"))
      (node (ref "C5") (pin "2") (pinfunction "2_2") (pintype "input"))
      (node (ref "CARD1") (pin "4") (pinfunction "VDD_4") (pintype "unspecified"))
      (node (ref "D1") (pin "1") (pinfunction "A_1") (pintype "unspecified"))
      (node (ref "D2") (pin "5") (pinfunction "VCC_5") (pintype "unspecified"))
      (node (ref "L1") (pin "1") (pinfunction "1_1") (pintype "unspecified"))
      (node (ref "LCD") (pin "3") (pinfunction "3_3") (pintype "unspecified"))
      (node (ref "PCA9685") (pin "1") (pinfunction "A0_1") (pintype "unspecified"))
      (node (ref "PCA9685") (pin "28") (pinfunction "VDD_28") (pintype "unspecified"))
      (node (ref "PCA9685") (pin "3") (pinfunction "A2_3") (pintype "unspecified"))
      (node (ref "PCA9685") (pin "5") (pinfunction "A4_5") (pintype "unspecified"))
      (node (ref "R1") (pin "2") (pinfunction "2_2") (pintype "input"))
      (node (ref "R23") (pin "2") (pinfunction "2_2") (pintype "input"))
      (node (ref "R24") (pin "2") (pinfunction "2_2") (pintype "input"))
      (node (ref "R5") (pin "1") (pinfunction "1_1") (pintype "input"))
      (node (ref "R6") (pin "1") (pinfunction "1_1") (pintype "input"))
      (node (ref "R7") (pin "1") (pinfunction "1_1") (pintype "input"))
      (node (ref "R8") (pin "1") (pinfunction "1_1") (pintype "input"))
      (node (ref "R9") (pin "1") (pinfunction "1_1") (pintype "input"))
      (node (ref "SWDEBUG") (pin "4") (pinfunction "4_4") (pintype "unspecified"))
      (node (ref "TB6612") (pin "20") (pinfunction "VCC_20") (pintype "unspecified"))
      (node (ref "U1") (pin "100") (pinfunction "VDD_100") (pintype "unspecified"))
      (node (ref "U1") (pin "11") (pinfunction "VDD_11") (pintype "unspecified"))
      (node (ref "U1") (pin "27") (pinfunction "VDD_27") (pintype "unspecified"))
      (node (ref "U1") (pin "50") (pinfunction "VDD_50") (pintype "unspecified"))
      (node (ref "U1") (pin "75") (pinfunction "VDD_75") (pintype "unspecified"))
      (node (ref "U2") (pin "2") (pinfunction "VOUT_2") (pintype "unspecified"))
    )
    (net (code "75") (name "VIN") (class "Default")
      (node (ref "R22") (pin "1") (pinfunction "1_1") (pintype "input"))
      (node (ref "U8") (pin "4") (pinfunction "4_4") (pintype "unspecified"))
      (node (ref "电机电源开关") (pin "1") (pinfunction "1_1") (pintype "input"))
    )
    (net (code "76") (name "unconnected-(BOOT0-Pad2)") (class "Default")
      (node (ref "BOOT0") (pin "2") (pinfunction "2_2") (pintype "unspecified+no_connect"))
    )
    (net (code "77") (name "unconnected-(BOOT0-Pad4)") (class "Default")
      (node (ref "BOOT0") (pin "4") (pinfunction "4_4") (pintype "unspecified+no_connect"))
    )
    (net (code "78") (name "unconnected-(KEY-Pad2)") (class "Default")
      (node (ref "KEY") (pin "2") (pinfunction "2_2") (pintype "unspecified+no_connect"))
    )
    (net (code "79") (name "unconnected-(KEY-Pad4)") (class "Default")
      (node (ref "KEY") (pin "4") (pinfunction "4_4") (pintype "unspecified+no_connect"))
    )
    (net (code "80") (name "unconnected-(LCD-Pad6)") (class "Default")
      (node (ref "LCD") (pin "6") (pinfunction "6_6") (pintype "unspecified+no_connect"))
    )
    (net (code "81") (name "unconnected-(LCD-Pad13)") (class "Default")
      (node (ref "LCD") (pin "13") (pinfunction "13_13") (pintype "unspecified+no_connect"))
    )
    (net (code "82") (name "unconnected-(LCD-Pad14)") (class "Default")
      (node (ref "LCD") (pin "14") (pinfunction "14_14") (pintype "unspecified+no_connect"))
    )
    (net (code "83") (name "unconnected-(PCA9685-LED3-Pad9)") (class "Default")
      (node (ref "PCA9685") (pin "9") (pinfunction "LED3_9") (pintype "unspecified+no_connect"))
    )
    (net (code "84") (name "unconnected-(PCA9685-LED4-Pad10)") (class "Default")
      (node (ref "PCA9685") (pin "10") (pinfunction "LED4_10") (pintype "unspecified+no_connect"))
    )
    (net (code "85") (name "unconnected-(PCA9685-LED5-Pad11)") (class "Default")
      (node (ref "PCA9685") (pin "11") (pinfunction "LED5_11") (pintype "unspecified+no_connect"))
    )
    (net (code "86") (name "unconnected-(PCA9685-LED6-Pad12)") (class "Default")
      (node (ref "PCA9685") (pin "12") (pinfunction "LED6_12") (pintype "unspecified+no_connect"))
    )
    (net (code "87") (name "unconnected-(PCA9685-LED7-Pad13)") (class "Default")
      (node (ref "PCA9685") (pin "13") (pinfunction "LED7_13") (pintype "unspecified+no_connect"))
    )
    (net (code "88") (name "unconnected-(PCA9685-LED8-Pad15)") (class "Default")
      (node (ref "PCA9685") (pin "15") (pinfunction "LED8_15") (pintype "unspecified+no_connect"))
    )
    (net (code "89") (name "unconnected-(PCA9685-LED9-Pad16)") (class "Default")
      (node (ref "PCA9685") (pin "16") (pinfunction "LED9_16") (pintype "unspecified+no_connect"))
    )
    (net (code "90") (name "unconnected-(PCA9685-LED10-Pad17)") (class "Default")
      (node (ref "PCA9685") (pin "17") (pinfunction "LED10_17") (pintype "unspecified+no_connect"))
    )
    (net (code "91") (name "unconnected-(PCA9685-LED11-Pad18)") (class "Default")
      (node (ref "PCA9685") (pin "18") (pinfunction "LED11_18") (pintype "unspecified+no_connect"))
    )
    (net (code "92") (name "unconnected-(PCA9685-LED12-Pad19)") (class "Default")
      (node (ref "PCA9685") (pin "19") (pinfunction "LED12_19") (pintype "unspecified+no_connect"))
    )
    (net (code "93") (name "unconnected-(PCA9685-LED13-Pad20)") (class "Default")
      (node (ref "PCA9685") (pin "20") (pinfunction "LED13_20") (pintype "unspecified+no_connect"))
    )
    (net (code "94") (name "unconnected-(PCA9685-LED14-Pad21)") (class "Default")
      (node (ref "PCA9685") (pin "21") (pinfunction "LED14_21") (pintype "unspecified+no_connect"))
    )
    (net (code "95") (name "unconnected-(PCA9685-LED15-Pad22)") (class "Default")
      (node (ref "PCA9685") (pin "22") (pinfunction "LED15_22") (pintype "unspecified+no_connect"))
    )
    (net (code "96") (name "unconnected-(RST-Pad2)") (class "Default")
      (node (ref "RST") (pin "2") (pinfunction "2_2") (pintype "unspecified+no_connect"))
    )
    (net (code "97") (name "unconnected-(RST-Pad4)") (class "Default")
      (node (ref "RST") (pin "4") (pinfunction "4_4") (pintype "unspecified+no_connect"))
    )
    (net (code "98") (name "unconnected-(U1-PA3-Pad25)") (class "Default")
      (node (ref "U1") (pin "25") (pinfunction "PA3_25") (pintype "unspecified"))
    )
    (net (code "99") (name "unconnected-(U1-PA4-Pad28)") (class "Default")
      (node (ref "U1") (pin "28") (pinfunction "PA4_28") (pintype "unspecified"))
    )
    (net (code "100") (name "unconnected-(U1-PA7-Pad31)") (class "Default")
      (node (ref "U1") (pin "31") (pinfunction "PA7_31") (pintype "unspecified"))
    )
    (net (code "101") (name "unconnected-(U1-PA8-Pad67)") (class "Default")
      (node (ref "U1") (pin "67") (pinfunction "PA8_67") (pintype "unspecified"))
    )
    (net (code "102") (name "unconnected-(U1-PB0-Pad34)") (class "Default")
      (node (ref "U1") (pin "34") (pinfunction "PB0_34") (pintype "unspecified"))
    )
    (net (code "103") (name "unconnected-(U1-PB1-Pad35)") (class "Default")
      (node (ref "U1") (pin "35") (pinfunction "PB1_35") (pintype "unspecified"))
    )
    (net (code "104") (name "unconnected-(U1-PB2-Pad36)") (class "Default")
      (node (ref "U1") (pin "36") (pinfunction "PB2_36") (pintype "unspecified"))
    )
    (net (code "105") (name "unconnected-(U1-PB3-Pad89)") (class "Default")
      (node (ref "U1") (pin "89") (pinfunction "PB3_89") (pintype "unspecified"))
    )
    (net (code "106") (name "unconnected-(U1-PB4-Pad90)") (class "Default")
      (node (ref "U1") (pin "90") (pinfunction "PB4_90") (pintype "unspecified"))
    )
    (net (code "107") (name "unconnected-(U1-PB5-Pad91)") (class "Default")
      (node (ref "U1") (pin "91") (pinfunction "PB5_91") (pintype "unspecified"))
    )
    (net (code "108") (name "unconnected-(U1-PB8-Pad95)") (class "Default")
      (node (ref "U1") (pin "95") (pinfunction "PB8_95") (pintype "unspecified"))
    )
    (net (code "109") (name "unconnected-(U1-PB9-Pad96)") (class "Default")
      (node (ref "U1") (pin "96") (pinfunction "PB9_96") (pintype "unspecified"))
    )
    (net (code "110") (name "unconnected-(U1-PB14-Pad53)") (class "Default")
      (node (ref "U1") (pin "53") (pinfunction "PB14_53") (pintype "unspecified"))
    )
    (net (code "111") (name "unconnected-(U1-PB15-Pad54)") (class "Default")
      (node (ref "U1") (pin "54") (pinfunction "PB15_54") (pintype "unspecified"))
    )
    (net (code "112") (name "unconnected-(U1-PC0-Pad15)") (class "Default")
      (node (ref "U1") (pin "15") (pinfunction "PC0_15") (pintype "unspecified"))
    )
    (net (code "113") (name "unconnected-(U1-PC2_C-Pad17)") (class "Default")
      (node (ref "U1") (pin "17") (pinfunction "PC2_C_17") (pintype "unspecified"))
    )
    (net (code "114") (name "unconnected-(U1-PC3_C-Pad18)") (class "Default")
      (node (ref "U1") (pin "18") (pinfunction "PC3_C_18") (pintype "unspecified"))
    )
    (net (code "115") (name "unconnected-(U1-PC4-Pad32)") (class "Default")
      (node (ref "U1") (pin "32") (pinfunction "PC4_32") (pintype "unspecified"))
    )
    (net (code "116") (name "unconnected-(U1-PC5-Pad33)") (class "Default")
      (node (ref "U1") (pin "33") (pinfunction "PC5_33") (pintype "unspecified"))
    )
    (net (code "117") (name "unconnected-(U1-PC13-Pad7)") (class "Default")
      (node (ref "U1") (pin "7") (pinfunction "PC13_7") (pintype "unspecified"))
    )
    (net (code "118") (name "unconnected-(U1-PD5-Pad86)") (class "Default")
      (node (ref "U1") (pin "86") (pinfunction "PD5_86") (pintype "unspecified"))
    )
    (net (code "119") (name "unconnected-(U1-PD6-Pad87)") (class "Default")
      (node (ref "U1") (pin "87") (pinfunction "PD6_87") (pintype "unspecified"))
    )
    (net (code "120") (name "unconnected-(U1-PD7-Pad88)") (class "Default")
      (node (ref "U1") (pin "88") (pinfunction "PD7_88") (pintype "unspecified"))
    )
    (net (code "121") (name "unconnected-(U1-PD8-Pad55)") (class "Default")
      (node (ref "U1") (pin "55") (pinfunction "PD8_55") (pintype "unspecified"))
    )
    (net (code "122") (name "unconnected-(U1-PD9-Pad56)") (class "Default")
      (node (ref "U1") (pin "56") (pinfunction "PD9_56") (pintype "unspecified"))
    )
    (net (code "123") (name "unconnected-(U1-PD10-Pad57)") (class "Default")
      (node (ref "U1") (pin "57") (pinfunction "PD10_57") (pintype "unspecified"))
    )
    (net (code "124") (name "unconnected-(U1-PD11-Pad58)") (class "Default")
      (node (ref "U1") (pin "58") (pinfunction "PD11_58") (pintype "unspecified"))
    )
    (net (code "125") (name "unconnected-(U1-PD14-Pad61)") (class "Default")
      (node (ref "U1") (pin "61") (pinfunction "PD14_61") (pintype "unspecified"))
    )
    (net (code "126") (name "unconnected-(U1-PD15-Pad62)") (class "Default")
      (node (ref "U1") (pin "62") (pinfunction "PD15_62") (pintype "unspecified"))
    )
    (net (code "127") (name "unconnected-(U1-PE0-Pad97)") (class "Default")
      (node (ref "U1") (pin "97") (pinfunction "PE0_97") (pintype "unspecified"))
    )
    (net (code "128") (name "unconnected-(U1-PE1-Pad98)") (class "Default")
      (node (ref "U1") (pin "98") (pinfunction "PE1_98") (pintype "unspecified"))
    )
    (net (code "129") (name "unconnected-(U1-PE2-Pad1)") (class "Default")
      (node (ref "U1") (pin "1") (pinfunction "PE2_1") (pintype "unspecified"))
    )
    (net (code "130") (name "unconnected-(U1-PE3-Pad2)") (class "Default")
      (node (ref "U1") (pin "2") (pinfunction "PE3_2") (pintype "unspecified"))
    )
    (net (code "131") (name "unconnected-(U1-PE4-Pad3)") (class "Default")
      (node (ref "U1") (pin "3") (pinfunction "PE4_3") (pintype "unspecified"))
    )
    (net (code "132") (name "unconnected-(U1-PE5-Pad4)") (class "Default")
      (node (ref "U1") (pin "4") (pinfunction "PE5_4") (pintype "unspecified"))
    )
    (net (code "133") (name "unconnected-(U1-PE6-Pad5)") (class "Default")
      (node (ref "U1") (pin "5") (pinfunction "PE6_5") (pintype "unspecified"))
    )
    (net (code "134") (name "unconnected-(U1-PE7-Pad37)") (class "Default")
      (node (ref "U1") (pin "37") (pinfunction "PE7_37") (pintype "unspecified"))
    )
    (net (code "135") (name "unconnected-(U1-PE8-Pad38)") (class "Default")
      (node (ref "U1") (pin "38") (pinfunction "PE8_38") (pintype "unspecified"))
    )
    (net (code "136") (name "unconnected-(U1-PE9-Pad39)") (class "Default")
      (node (ref "U1") (pin "39") (pinfunction "PE9_39") (pintype "unspecified"))
    )
    (net (code "137") (name "unconnected-(U1-PE10-Pad40)") (class "Default")
      (node (ref "U1") (pin "40") (pinfunction "PE10_40") (pintype "unspecified"))
    )
    (net (code "138") (name "unconnected-(U1-PE11-Pad41)") (class "Default")
      (node (ref "U1") (pin "41") (pinfunction "PE11_41") (pintype "unspecified"))
    )
    (net (code "139") (name "unconnected-(U1-PE12-Pad42)") (class "Default")
      (node (ref "U1") (pin "42") (pinfunction "PE12_42") (pintype "unspecified"))
    )
    (net (code "140") (name "unconnected-(U1-PE13-Pad43)") (class "Default")
      (node (ref "U1") (pin "43") (pinfunction "PE13_43") (pintype "unspecified"))
    )
    (net (code "141") (name "unconnected-(U2-VOUT-Pad4)") (class "Default")
      (node (ref "U2") (pin "4") (pinfunction "VOUT_4") (pintype "unspecified+no_connect"))
    )
    (net (code "142") (name "unconnected-(U7-A-Pad10)") (class "Default")
      (node (ref "U7") (pin "10") (pinfunction "A_10") (pintype "unspecified+no_connect"))
    )
    (net (code "143") (name "unconnected-(U7-CS-Pad2)") (class "Default")
      (node (ref "U7") (pin "2") (pinfunction "CS_2") (pintype "unspecified+no_connect"))
    )
    (net (code "144") (name "unconnected-(U7-GND-Pad1)") (class "Default")
      (node (ref "U7") (pin "1") (pinfunction "GND_1") (pintype "unspecified+no_connect"))
    )
    (net (code "145") (name "unconnected-(U7-GND-Pad12)") (class "Default")
      (node (ref "U7") (pin "12") (pinfunction "GND_12") (pintype "unspecified+no_connect"))
    )
    (net (code "146") (name "unconnected-(U7-I{slash}O-VCC-Pad8)") (class "Default")
      (node (ref "U7") (pin "8") (pinfunction "I/O-VCC_8") (pintype "unspecified+no_connect"))
    )
    (net (code "147") (name "unconnected-(U7-K-Pad11)") (class "Default")
      (node (ref "U7") (pin "11") (pinfunction "K_11") (pintype "unspecified+no_connect"))
    )
    (net (code "148") (name "unconnected-(U7-NC-Pad7)") (class "Default")
      (node (ref "U7") (pin "7") (pinfunction "NC_7") (pintype "unspecified+no_connect"))
    )
    (net (code "149") (name "unconnected-(U7-RS-Pad3)") (class "Default")
      (node (ref "U7") (pin "3") (pinfunction "RS_3") (pintype "unspecified+no_connect"))
    )
    (net (code "150") (name "unconnected-(U7-RST-Pad6)") (class "Default")
      (node (ref "U7") (pin "6") (pinfunction "RST_6") (pintype "unspecified+no_connect"))
    )
    (net (code "151") (name "unconnected-(U7-SCL-Pad4)") (class "Default")
      (node (ref "U7") (pin "4") (pinfunction "SCL_4") (pintype "unspecified+no_connect"))
    )
    (net (code "152") (name "unconnected-(U7-SDA-Pad5)") (class "Default")
      (node (ref "U7") (pin "5") (pinfunction "SDA_5") (pintype "unspecified+no_connect"))
    )
    (net (code "153") (name "unconnected-(U7-VCC-Pad9)") (class "Default")
      (node (ref "U7") (pin "9") (pinfunction "VCC_9") (pintype "unspecified+no_connect"))
    )
    (net (code "154") (name "unconnected-(USB1-SBU1-PadA8)") (class "Default")
      (node (ref "USB1") (pin "A8") (pinfunction "SBU1_A8") (pintype "unspecified+no_connect"))
    )
    (net (code "155") (name "unconnected-(USB1-SBU2-PadB8)") (class "Default")
      (node (ref "USB1") (pin "B8") (pinfunction "SBU2_B8") (pintype "unspecified+no_connect"))
    )
  )
)
